# microscope_board.net
KiCad netlist of a schematic drawn in EAGLE
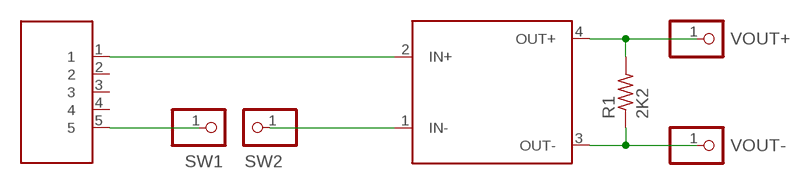
[diagram p0: schematic, sheet 1]

(export (version "E")
  (design (tool "Eeschema 10.0.6"))
  (components
    (comp (ref "R1")
      (value "2K2")
      (footprint "eagle-import:R0805")
      (libsource (lib "eagle-import") (part "R-US_R0805"))
    )
    (comp (ref "SW1")
      (value "PINHD-1X1")
      (footprint "eagle-import:1X01")
      (libsource (lib "eagle-import") (part "PINHD-1X1"))
    )
    (comp (ref "SW2")
      (value "PINHD-1X1")
      (footprint "eagle-import:1X01")
      (libsource (lib "eagle-import") (part "PINHD-1X1"))
    )
    (comp (ref "U$1")
      (value "DC_DC")
      (footprint "eagle-import:DC_DC")
      (libsource (lib "eagle-import") (part "DC_DC"))
    )
    (comp (ref "U$2")
      (value "USB_CONNECTOR")
      (footprint "eagle-import:USB_CONNECTOR")
      (libsource (lib "eagle-import") (part "USB_CONNECTOR"))
    )
    (comp (ref "VOUT+")
      (value "PINHD-1X1")
      (footprint "eagle-import:1X01")
      (libsource (lib "eagle-import") (part "PINHD-1X1"))
    )
    (comp (ref "VOUT-")
      (value "PINHD-1X1")
      (footprint "eagle-import:1X01")
      (libsource (lib "eagle-import") (part "PINHD-1X1"))
    )
  )
  (nets
    (net (code "1") (name "Net-(SW1-Pad1)") (class "Default")
      (node (ref "SW1") (pin "1") (pinfunction "1_1") (pintype "passive"))
      (node (ref "U$2") (pin "5") (pinfunction "5_5") (pintype "bidirectional"))
    )
    (net (code "2") (name "Net-(U$1-IN+)") (class "Default")
      (node (ref "U$1") (pin "2") (pinfunction "IN+_2") (pintype "bidirectional"))
      (node (ref "U$2") (pin "1") (pinfunction "1_1") (pintype "bidirectional"))
    )
    (net (code "3") (name "Net-(U$1-IN-)") (class "Default")
      (node (ref "SW2") (pin "1") (pinfunction "1_1") (pintype "passive"))
      (node (ref "U$1") (pin "1") (pinfunction "IN-_1") (pintype "bidirectional"))
    )
    (net (code "4") (name "Net-(U$1-OUT+)") (class "Default")
      (node (ref "R1") (pin "2") (pinfunction "2_2") (pintype "passive"))
      (node (ref "U$1") (pin "4") (pinfunction "OUT+_4") (pintype "bidirectional"))
      (node (ref "VOUT+") (pin "1") (pinfunction "1_1") (pintype "passive"))
    )
    (net (code "5") (name "Net-(U$1-OUT-)") (class "Default")
      (node (ref "R1") (pin "1") (pinfunction "1_1") (pintype "passive"))
      (node (ref "U$1") (pin "3") (pinfunction "OUT-_3") (pintype "bidirectional"))
      (node (ref "VOUT-") (pin "1") (pinfunction "1_1") (pintype "passive"))
    )
    (net (code "6") (name "unconnected-(U$2-Pad2)") (class "Default")
      (node (ref "U$2") (pin "2") (pinfunction "2_2") (pintype "bidirectional"))
    )
    (net (code "7") (name "unconnected-(U$2-Pad3)") (class "Default")
      (node (ref "U$2") (pin "3") (pinfunction "3_3") (pintype "bidirectional"))
    )
    (net (code "8") (name "unconnected-(U$2-Pad4)") (class "Default")
      (node (ref "U$2") (pin "4") (pinfunction "4_4") (pintype "bidirectional"))
    )
  )
)
